# Schematic_V0_0.net
KiCad netlist of a schematic drawn in EAGLE
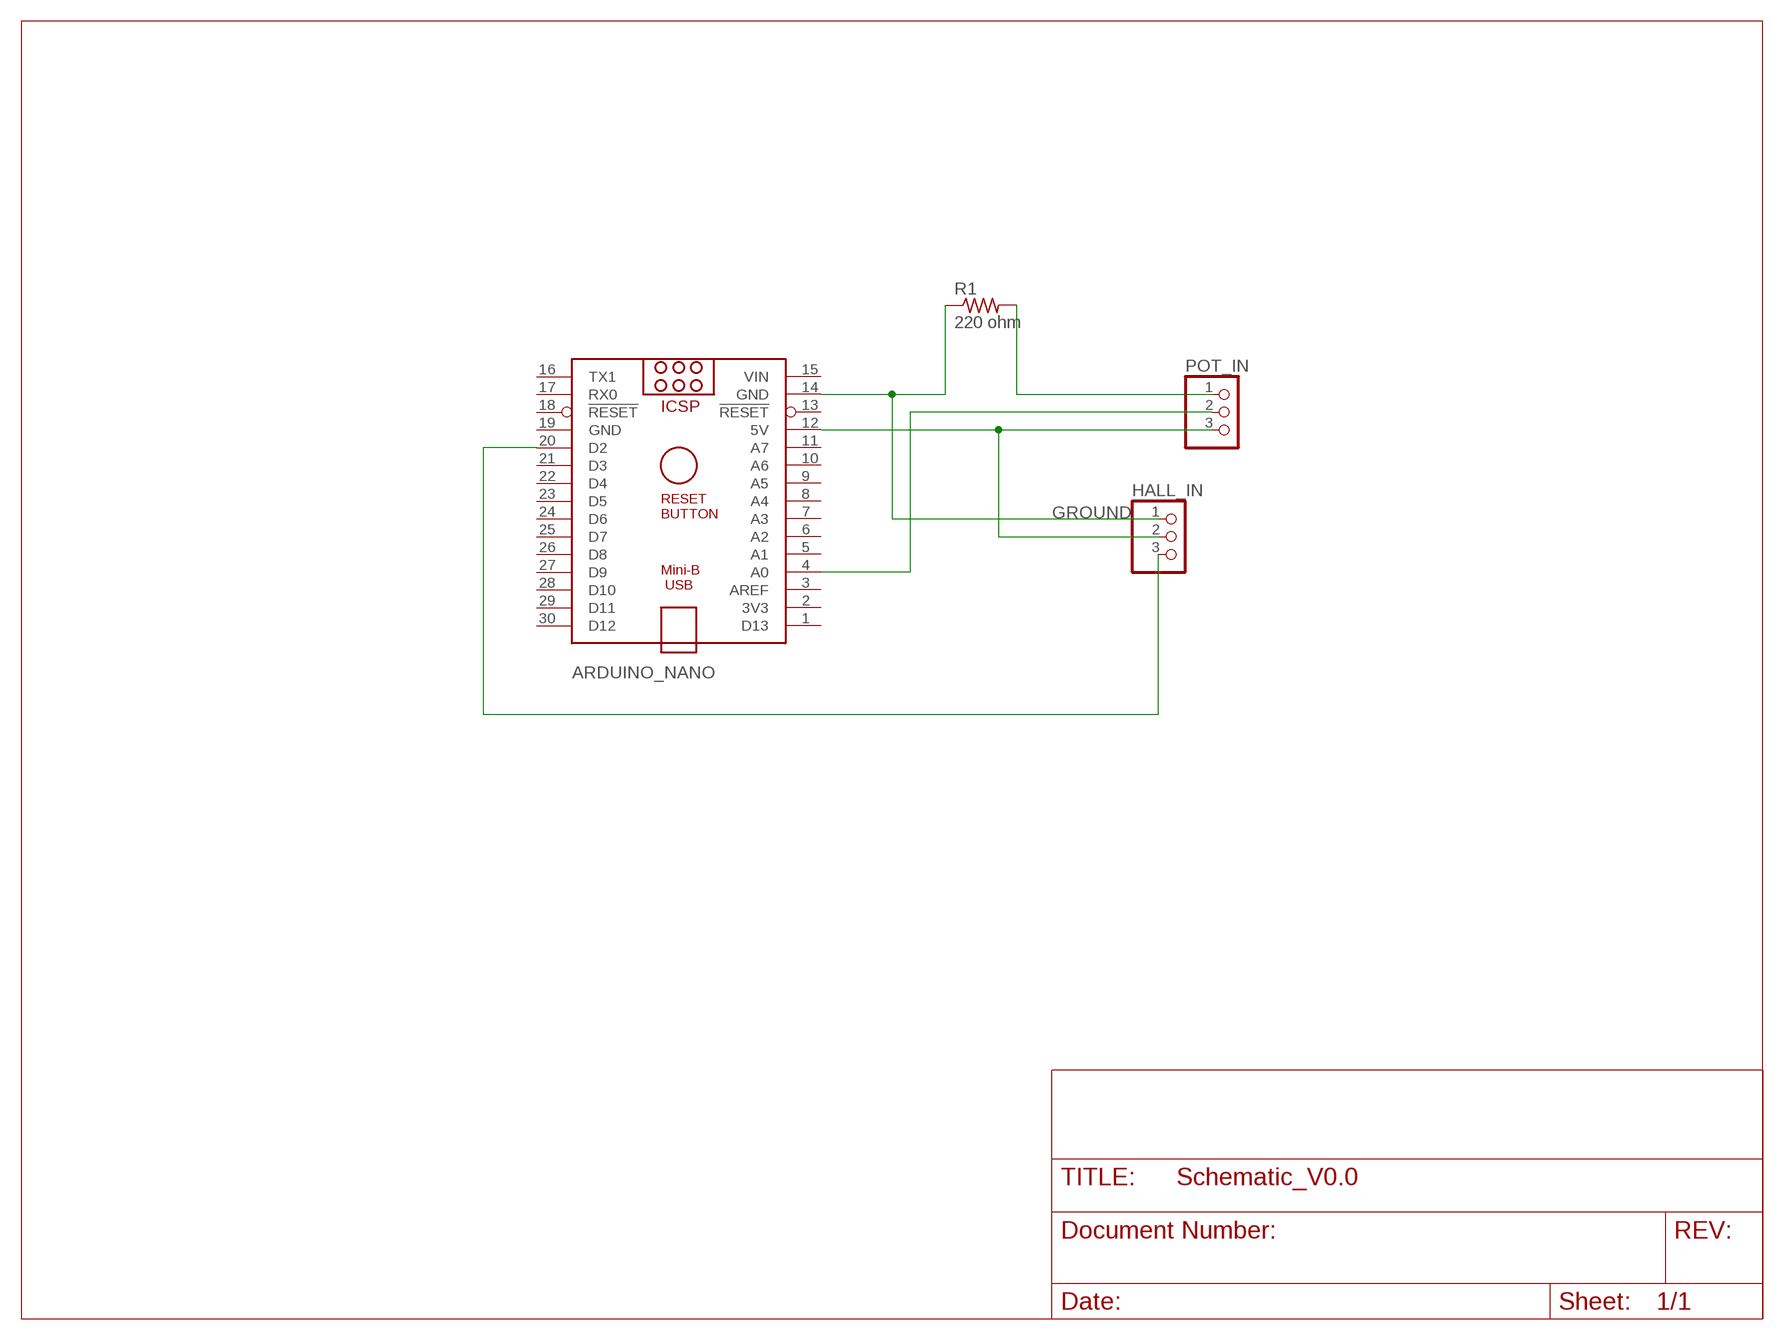
[diagram p0: schematic, sheet 1]

(export (version "E")
  (design (tool "Eeschema 10.0.6"))
  (components
    (comp (ref "ARDUINO_NANO")
      (value "ARDUINO_NANO")
      (footprint "eagle-import:ARDUINO_NANO")
      (libsource (lib "eagle-import") (part "ARDUINO_NANO"))
    )
    (comp (ref "HALL_IN")
      (value "PINHD-1X3")
      (footprint "eagle-import:1X03")
      (libsource (lib "eagle-import") (part "PINHD-1X3"))
    )
    (comp (ref "POT_IN")
      (value "PINHD-1X3")
      (footprint "eagle-import:1X03")
      (libsource (lib "eagle-import") (part "PINHD-1X3"))
    )
    (comp (ref "R1")
      (value "220 ohm")
      (footprint "eagle-import:0204_7")
      (libsource (lib "eagle-import") (part "R-US_0204/7"))
    )
  )
  (nets
    (net (code "1") (name "/GND") (class "Default")
      (node (ref "ARDUINO_NANO") (pin "19") (pinfunction "GND_19") (pintype "power_in"))
    )
    (net (code "2") (name "/GROUND") (class "Default")
      (node (ref "ARDUINO_NANO") (pin "14") (pinfunction "GND_14") (pintype "power_in"))
      (node (ref "HALL_IN") (pin "1") (pinfunction "1_1") (pintype "passive"))
      (node (ref "R1") (pin "1") (pinfunction "1_1") (pintype "passive"))
    )
    (net (code "3") (name "/VIN") (class "Default")
      (node (ref "ARDUINO_NANO") (pin "15") (pinfunction "VIN_15") (pintype "power_in"))
    )
    (net (code "4") (name "Net-(ARDUINO_NANO-5V)") (class "Default")
      (node (ref "ARDUINO_NANO") (pin "12") (pinfunction "5V_12") (pintype "power_in"))
      (node (ref "HALL_IN") (pin "2") (pinfunction "2_2") (pintype "passive"))
      (node (ref "POT_IN") (pin "3") (pinfunction "3_3") (pintype "passive"))
    )
    (net (code "5") (name "Net-(ARDUINO_NANO-A0)") (class "Default")
      (node (ref "ARDUINO_NANO") (pin "4") (pinfunction "A0_4") (pintype "bidirectional"))
      (node (ref "POT_IN") (pin "2") (pinfunction "2_2") (pintype "passive"))
    )
    (net (code "6") (name "Net-(ARDUINO_NANO-D2)") (class "Default")
      (node (ref "ARDUINO_NANO") (pin "20") (pinfunction "D2_20") (pintype "bidirectional"))
      (node (ref "HALL_IN") (pin "3") (pinfunction "3_3") (pintype "passive"))
    )
    (net (code "7") (name "Net-(POT_IN-Pad1)") (class "Default")
      (node (ref "POT_IN") (pin "1") (pinfunction "1_1") (pintype "passive"))
      (node (ref "R1") (pin "2") (pinfunction "2_2") (pintype "passive"))
    )
    (net (code "8") (name "unconnected-(ARDUINO_NANO-3V3-Pad2)") (class "Default")
      (node (ref "ARDUINO_NANO") (pin "2") (pinfunction "3V3_2") (pintype "output"))
    )
    (net (code "9") (name "unconnected-(ARDUINO_NANO-A1-Pad5)") (class "Default")
      (node (ref "ARDUINO_NANO") (pin "5") (pinfunction "A1_5") (pintype "bidirectional"))
    )
    (net (code "10") (name "unconnected-(ARDUINO_NANO-A2-Pad6)") (class "Default")
      (node (ref "ARDUINO_NANO") (pin "6") (pinfunction "A2_6") (pintype "bidirectional"))
    )
    (net (code "11") (name "unconnected-(ARDUINO_NANO-A3-Pad7)") (class "Default")
      (node (ref "ARDUINO_NANO") (pin "7") (pinfunction "A3_7") (pintype "bidirectional"))
    )
    (net (code "12") (name "unconnected-(ARDUINO_NANO-A4-Pad8)") (class "Default")
      (node (ref "ARDUINO_NANO") (pin "8") (pinfunction "A4_8") (pintype "bidirectional"))
    )
    (net (code "13") (name "unconnected-(ARDUINO_NANO-A5-Pad9)") (class "Default")
      (node (ref "ARDUINO_NANO") (pin "9") (pinfunction "A5_9") (pintype "bidirectional"))
    )
    (net (code "14") (name "unconnected-(ARDUINO_NANO-A6-Pad10)") (class "Default")
      (node (ref "ARDUINO_NANO") (pin "10") (pinfunction "A6_10") (pintype "bidirectional"))
    )
    (net (code "15") (name "unconnected-(ARDUINO_NANO-A7-Pad11)") (class "Default")
      (node (ref "ARDUINO_NANO") (pin "11") (pinfunction "A7_11") (pintype "bidirectional"))
    )
    (net (code "16") (name "unconnected-(ARDUINO_NANO-AREF-Pad3)") (class "Default")
      (node (ref "ARDUINO_NANO") (pin "3") (pinfunction "AREF_3") (pintype "input"))
    )
    (net (code "17") (name "unconnected-(ARDUINO_NANO-D3-Pad21)") (class "Default")
      (node (ref "ARDUINO_NANO") (pin "21") (pinfunction "D3_21") (pintype "bidirectional"))
    )
    (net (code "18") (name "unconnected-(ARDUINO_NANO-D4-Pad22)") (class "Default")
      (node (ref "ARDUINO_NANO") (pin "22") (pinfunction "D4_22") (pintype "bidirectional"))
    )
    (net (code "19") (name "unconnected-(ARDUINO_NANO-D5-Pad23)") (class "Default")
      (node (ref "ARDUINO_NANO") (pin "23") (pinfunction "D5_23") (pintype "bidirectional"))
    )
    (net (code "20") (name "unconnected-(ARDUINO_NANO-D6-Pad24)") (class "Default")
      (node (ref "ARDUINO_NANO") (pin "24") (pinfunction "D6_24") (pintype "bidirectional"))
    )
    (net (code "21") (name "unconnected-(ARDUINO_NANO-D7-Pad25)") (class "Default")
      (node (ref "ARDUINO_NANO") (pin "25") (pinfunction "D7_25") (pintype "bidirectional"))
    )
    (net (code "22") (name "unconnected-(ARDUINO_NANO-D8-Pad26)") (class "Default")
      (node (ref "ARDUINO_NANO") (pin "26") (pinfunction "D8_26") (pintype "bidirectional"))
    )
    (net (code "23") (name "unconnected-(ARDUINO_NANO-D9-Pad27)") (class "Default")
      (node (ref "ARDUINO_NANO") (pin "27") (pinfunction "D9_27") (pintype "bidirectional"))
    )
    (net (code "24") (name "unconnected-(ARDUINO_NANO-D10-Pad28)") (class "Default")
      (node (ref "ARDUINO_NANO") (pin "28") (pinfunction "D10_28") (pintype "bidirectional"))
    )
    (net (code "25") (name "unconnected-(ARDUINO_NANO-D11-Pad29)") (class "Default")
      (node (ref "ARDUINO_NANO") (pin "29") (pinfunction "D11_29") (pintype "bidirectional"))
    )
    (net (code "26") (name "unconnected-(ARDUINO_NANO-D12-Pad30)") (class "Default")
      (node (ref "ARDUINO_NANO") (pin "30") (pinfunction "D12_30") (pintype "bidirectional"))
    )
    (net (code "27") (name "unconnected-(ARDUINO_NANO-D13-Pad1)") (class "Default")
      (node (ref "ARDUINO_NANO") (pin "1") (pinfunction "D13_1") (pintype "bidirectional"))
    )
    (net (code "28") (name "unconnected-(ARDUINO_NANO-RX0-Pad17)") (class "Default")
      (node (ref "ARDUINO_NANO") (pin "17") (pinfunction "RX0_17") (pintype "bidirectional"))
    )
    (net (code "29") (name "unconnected-(ARDUINO_NANO-TX1-Pad16)") (class "Default")
      (node (ref "ARDUINO_NANO") (pin "16") (pinfunction "TX1_16") (pintype "bidirectional"))
    )
    (net (code "30") (name "unconnected-(ARDUINO_NANO-~{RESET}-Pad13)") (class "Default")
      (node (ref "ARDUINO_NANO") (pin "13") (pinfunction "~{RESET}_13") (pintype "input"))
    )
    (net (code "31") (name "unconnected-(ARDUINO_NANO-~{RESET}-Pad18)") (class "Default")
      (node (ref "ARDUINO_NANO") (pin "18") (pinfunction "~{RESET}_18") (pintype "input"))
    )
  )
)
